# HV_Sense.net
KiCad netlist of a schematic drawn in Altium Designer
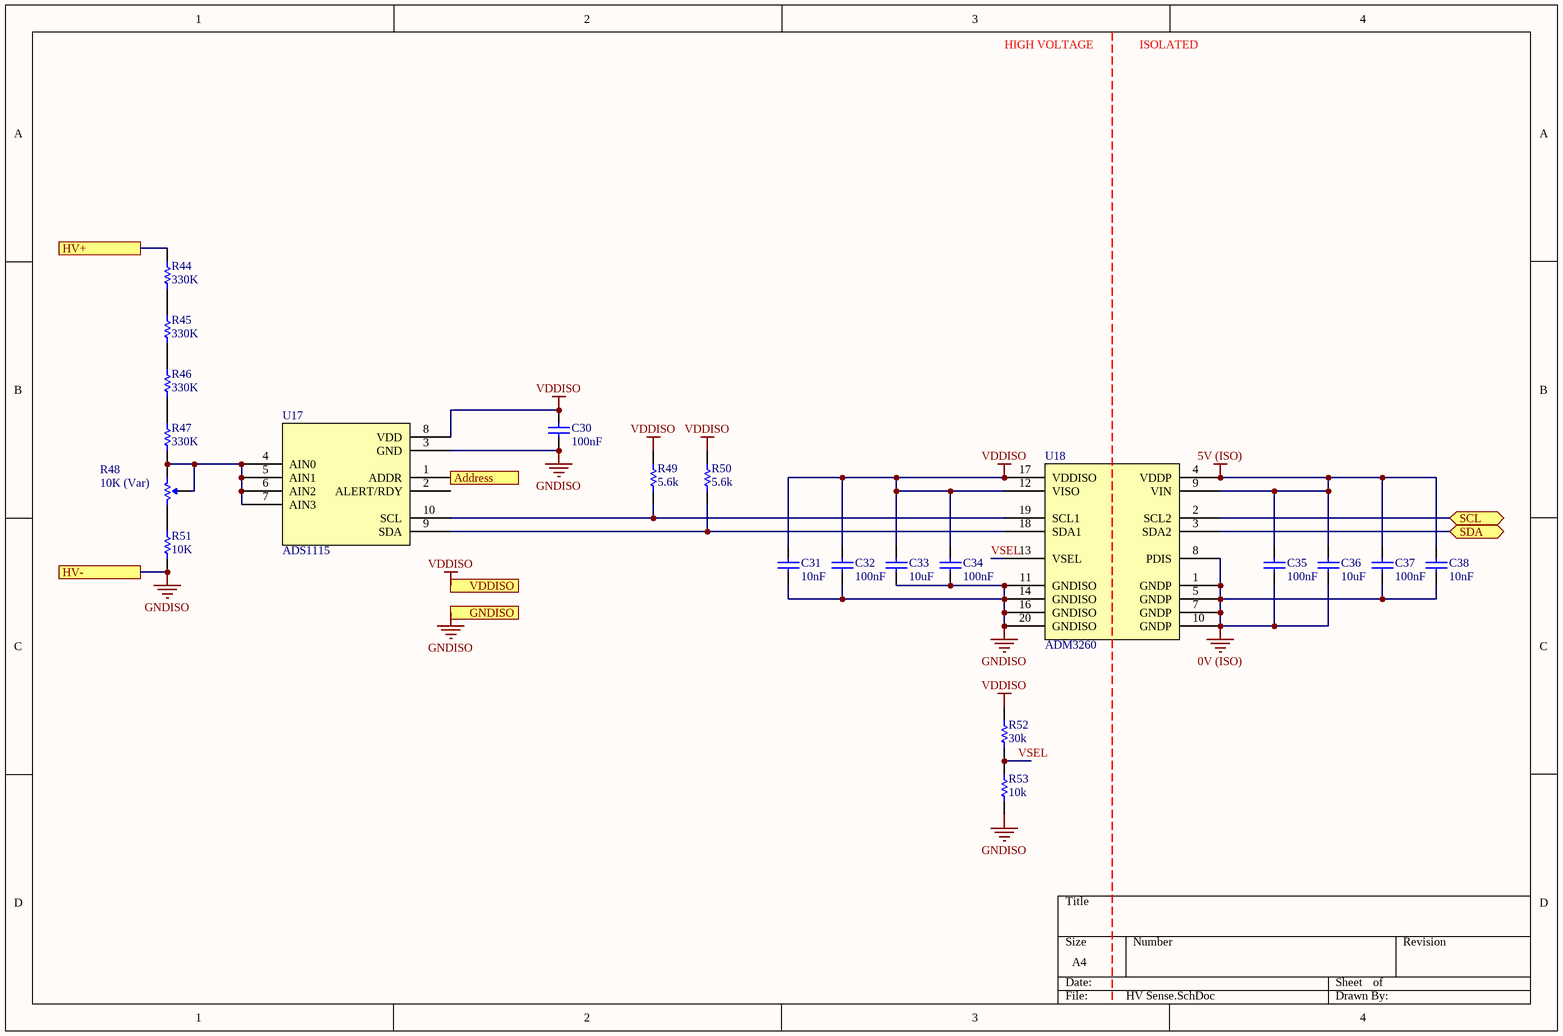
[diagram p0: HV Sense.SchDoc]

(export (version "E")
  (design (tool "Eeschema 10.0.6"))
  (components
    (comp (ref "C30")
      (value "100nF")
      (footprint "0805")
      (fields
        (field (name "PART NUMBER") "GCM21BR71E104KA37L")
        (field (name "TOLERANCE") "10%")
        (field (name "MANUFACTURER") "muRata")
      )
      (libsource (lib "ts_20-standard-library") (part "Capacitor"))
    )
    (comp (ref "C31")
      (value "10nF")
      (footprint "0805")
      (fields
        (field (name "PART NUMBER") "GCM21BR71H103KA37L")
        (field (name "TOLERANCE") "10%")
        (field (name "MANUFACTURER") "muRata")
      )
      (libsource (lib "ts_20-standard-library") (part "Capacitor"))
    )
    (comp (ref "C32")
      (value "100nF")
      (footprint "0805")
      (fields
        (field (name "PART NUMBER") "GCM21BR71E104KA37L")
        (field (name "TOLERANCE") "10%")
        (field (name "MANUFACTURER") "muRata")
      )
      (libsource (lib "ts_20-standard-library") (part "Capacitor"))
    )
    (comp (ref "C33")
      (value "10uF")
      (footprint "0805")
      (fields
        (field (name "PART NUMBER") "GRM21BR6YA106KE43L")
        (field (name "TOLERANCE") "10%")
        (field (name "MANUFACTURER") "muRata")
      )
      (libsource (lib "ts_20-standard-library") (part "Capacitor"))
    )
    (comp (ref "C34")
      (value "100nF")
      (footprint "0805")
      (fields
        (field (name "PART NUMBER") "GCM21BR71E104KA37L")
        (field (name "TOLERANCE") "10%")
        (field (name "MANUFACTURER") "muRata")
      )
      (libsource (lib "ts_20-standard-library") (part "Capacitor"))
    )
    (comp (ref "C35")
      (value "100nF")
      (footprint "0805")
      (fields
        (field (name "PART NUMBER") "GCM21BR71E104KA37L")
        (field (name "TOLERANCE") "10%")
        (field (name "MANUFACTURER") "muRata")
      )
      (libsource (lib "ts_20-standard-library") (part "Capacitor"))
    )
    (comp (ref "C36")
      (value "10uF")
      (footprint "0805")
      (fields
        (field (name "PART NUMBER") "GRM21BR6YA106KE43L")
        (field (name "TOLERANCE") "10%")
        (field (name "MANUFACTURER") "muRata")
      )
      (libsource (lib "ts_20-standard-library") (part "Capacitor"))
    )
    (comp (ref "C37")
      (value "100nF")
      (footprint "0805")
      (fields
        (field (name "PART NUMBER") "GCM21BR71E104KA37L")
        (field (name "TOLERANCE") "10%")
        (field (name "MANUFACTURER") "muRata")
      )
      (libsource (lib "ts_20-standard-library") (part "Capacitor"))
    )
    (comp (ref "C38")
      (value "10nF")
      (footprint "0805")
      (fields
        (field (name "PART NUMBER") "GCM21BR71H103KA37L")
        (field (name "TOLERANCE") "10%")
        (field (name "MANUFACTURER") "muRata")
      )
      (libsource (lib "ts_20-standard-library") (part "Capacitor"))
    )
    (comp (ref "R44")
      (value "330K")
      (footprint "VB 0204")
      (fields
        (field (name "PART NUMBER") "MMA02040C3303FB300")
        (field (name "MANUFACTURER") "Vishay Beyschlag")
        (field (name "TOLERANCE") "0.01")
      )
      (libsource (lib "ts_20-standard-library") (part "Resistor"))
    )
    (comp (ref "R45")
      (value "330K")
      (footprint "VB 0204")
      (fields
        (field (name "PART NUMBER") "MMA02040C3303FB300")
        (field (name "MANUFACTURER") "Vishay Beyschlag")
        (field (name "TOLERANCE") "0.01")
      )
      (libsource (lib "ts_20-standard-library") (part "Resistor"))
    )
    (comp (ref "R46")
      (value "330K")
      (footprint "VB 0204")
      (fields
        (field (name "PART NUMBER") "MMA02040C3303FB300")
        (field (name "MANUFACTURER") "Vishay Beyschlag")
        (field (name "TOLERANCE") "0.01")
      )
      (libsource (lib "ts_20-standard-library") (part "Resistor"))
    )
    (comp (ref "R47")
      (value "330K")
      (footprint "VB 0204")
      (fields
        (field (name "PART NUMBER") "MMA02040C3303FB300")
        (field (name "MANUFACTURER") "Vishay Beyschlag")
        (field (name "TOLERANCE") "0.01")
      )
      (libsource (lib "ts_20-standard-library") (part "Resistor"))
    )
    (comp (ref "R48")
      (value "10K (Var)")
      (footprint "B 3296")
      (fields
        (field (name "PART NUMBER") "3296W-1-103LF")
        (field (name "MANUFACTURER") "Bournes Inc")
        (field (name "TOLERANCE") "0.1")
      )
      (libsource (lib "ts_20-standard-library") (part "Resistor (Potentiometer)"))
    )
    (comp (ref "R49")
      (value "5.6k")
      (footprint "0805")
      (fields
        (field (name "PART NUMBER") "RC0805FR075K6L")
        (field (name "MANUFACTURER") "YAGEO")
        (field (name "TOLERANCE") "0.01")
      )
      (libsource (lib "ts_20-standard-library") (part "Resistor"))
    )
    (comp (ref "R50")
      (value "5.6k")
      (footprint "0805")
      (fields
        (field (name "PART NUMBER") "RC0805FR075K6L")
        (field (name "MANUFACTURER") "YAGEO")
        (field (name "TOLERANCE") "0.01")
      )
      (libsource (lib "ts_20-standard-library") (part "Resistor"))
    )
    (comp (ref "R51")
      (value "10K")
      (footprint "VB 0204")
      (fields
        (field (name "PART NUMBER") "MMA02040C1002FB300")
        (field (name "MANUFACTURER") "Vishay Beyschlag")
        (field (name "TOLERANCE") "0.01")
      )
      (libsource (lib "ts_20-standard-library") (part "Resistor"))
    )
    (comp (ref "R52")
      (value "30k")
      (footprint "0805")
      (fields
        (field (name "PART NUMBER") "RC0805FR0730KL")
        (field (name "MANUFACTURER") "YAGEO")
        (field (name "TOLERANCE") "0.01")
      )
      (libsource (lib "ts_20-standard-library") (part "Resistor"))
    )
    (comp (ref "R53")
      (value "10k")
      (footprint "0805")
      (fields
        (field (name "PART NUMBER") "RC0805FR0710KL")
        (field (name "MANUFACTURER") "YAGEO")
        (field (name "TOLERANCE") "0.01")
      )
      (libsource (lib "ts_20-standard-library") (part "Resistor"))
    )
    (comp (ref "U17")
      (value "ADS1115")
      (footprint "TI 10-VSSOP")
      (description "16 Bit Analog to Digital Converter 2, 4 Input 1 Sigma-Delta 10-VSSOP")
      (fields
        (field (name "MANUFACTURER") "Texas Instruments")
        (field (name "DIGIKEY PART NUMBER") "296-38849-1-ND")
      )
      (libsource (lib "ts_20-standard-library") (part "ADS1115"))
    )
    (comp (ref "U18")
      (value "ADM3260")
      (footprint "AD 20-SSOP")
      (description "I²C Digital Isolator 2500Vrms 2 Channel 25kV/µs CMTI 20-SSOP (0.209\", 5.30mm Width)")
      (fields
        (field (name "MANUFACTURER") "Analog Devices")
        (field (name "DIGIKEY PART NUMBER") "ADM3260ARSZ-RL7CT-ND")
      )
      (libsource (lib "ts_20-standard-library") (part "ADM3260"))
    )
  )
  (nets
    (net (code "1") (name "/Address") (class "Default")
      (node (ref "U17") (pin "1") (pinfunction "ADDR_1") (pintype "passive"))
    )
    (net (code "2") (name "/HV+") (class "Default")
      (node (ref "R44") (pin "2") (pinfunction "2_2") (pintype "passive"))
    )
    (net (code "3") (name "/SCL") (class "Default")
      (node (ref "U18") (pin "2") (pinfunction "SCL2_2") (pintype "passive"))
    )
    (net (code "4") (name "/SDA") (class "Default")
      (node (ref "U18") (pin "3") (pinfunction "SDA2_3") (pintype "passive"))
    )
    (net (code "5") (name "/VSEL") (class "Default")
      (node (ref "R52") (pin "1") (pinfunction "1_1") (pintype "passive"))
      (node (ref "R53") (pin "2") (pinfunction "2_2") (pintype "passive"))
      (node (ref "U18") (pin "13") (pinfunction "VSEL_13") (pintype "passive"))
    )
    (net (code "6") (name "0V (ISO)") (class "Default")
      (node (ref "C35") (pin "1") (pinfunction "1_1") (pintype "passive"))
      (node (ref "C36") (pin "1") (pinfunction "1_1") (pintype "passive"))
      (node (ref "C37") (pin "1") (pinfunction "1_1") (pintype "passive"))
      (node (ref "C38") (pin "1") (pinfunction "1_1") (pintype "passive"))
      (node (ref "U18") (pin "1") (pinfunction "GNDP_1") (pintype "passive"))
      (node (ref "U18") (pin "10") (pinfunction "GNDP_10") (pintype "passive"))
      (node (ref "U18") (pin "5") (pinfunction "GNDP_5") (pintype "passive"))
      (node (ref "U18") (pin "7") (pinfunction "GNDP_7") (pintype "passive"))
      (node (ref "U18") (pin "8") (pinfunction "PDIS_8") (pintype "passive"))
    )
    (net (code "7") (name "5V (ISO)") (class "Default")
      (node (ref "C35") (pin "2") (pinfunction "2_2") (pintype "passive"))
      (node (ref "C36") (pin "2") (pinfunction "2_2") (pintype "passive"))
      (node (ref "C37") (pin "2") (pinfunction "2_2") (pintype "passive"))
      (node (ref "C38") (pin "2") (pinfunction "2_2") (pintype "passive"))
      (node (ref "U18") (pin "4") (pinfunction "VDDP_4") (pintype "passive"))
      (node (ref "U18") (pin "9") (pinfunction "VIN_9") (pintype "passive"))
    )
    (net (code "8") (name "GNDISO") (class "Default")
      (node (ref "C30") (pin "2") (pinfunction "2_2") (pintype "passive"))
      (node (ref "C31") (pin "1") (pinfunction "1_1") (pintype "passive"))
      (node (ref "C32") (pin "1") (pinfunction "1_1") (pintype "passive"))
      (node (ref "C33") (pin "1") (pinfunction "1_1") (pintype "passive"))
      (node (ref "C34") (pin "2") (pinfunction "2_2") (pintype "passive"))
      (node (ref "R51") (pin "1") (pinfunction "1_1") (pintype "passive"))
      (node (ref "R53") (pin "1") (pinfunction "1_1") (pintype "passive"))
      (node (ref "U17") (pin "3") (pinfunction "GND_3") (pintype "passive"))
      (node (ref "U18") (pin "11") (pinfunction "GNDISO_11") (pintype "passive"))
      (node (ref "U18") (pin "14") (pinfunction "GNDISO_14") (pintype "passive"))
      (node (ref "U18") (pin "16") (pinfunction "GNDISO_16") (pintype "passive"))
      (node (ref "U18") (pin "20") (pinfunction "GNDISO_20") (pintype "passive"))
    )
    (net (code "9") (name "Net-(R44-Pad1)") (class "Default")
      (node (ref "R44") (pin "1") (pinfunction "1_1") (pintype "passive"))
      (node (ref "R45") (pin "2") (pinfunction "2_2") (pintype "passive"))
    )
    (net (code "10") (name "Net-(R45-Pad1)") (class "Default")
      (node (ref "R45") (pin "1") (pinfunction "1_1") (pintype "passive"))
      (node (ref "R46") (pin "2") (pinfunction "2_2") (pintype "passive"))
    )
    (net (code "11") (name "Net-(R46-Pad1)") (class "Default")
      (node (ref "R46") (pin "1") (pinfunction "1_1") (pintype "passive"))
      (node (ref "R47") (pin "2") (pinfunction "2_2") (pintype "passive"))
    )
    (net (code "12") (name "Net-(R48-CCW)") (class "Default")
      (node (ref "R48") (pin "1") (pinfunction "CCW_1") (pintype "passive"))
      (node (ref "R51") (pin "2") (pinfunction "2_2") (pintype "passive"))
    )
    (net (code "13") (name "Net-(R48-CW)") (class "Default")
      (node (ref "R47") (pin "1") (pinfunction "1_1") (pintype "passive"))
      (node (ref "R48") (pin "2") (pinfunction "Wiper_2") (pintype "passive"))
      (node (ref "R48") (pin "3") (pinfunction "CW_3") (pintype "passive"))
      (node (ref "U17") (pin "4") (pinfunction "AIN0_4") (pintype "passive"))
      (node (ref "U17") (pin "5") (pinfunction "AIN1_5") (pintype "passive"))
      (node (ref "U17") (pin "6") (pinfunction "AIN2_6") (pintype "passive"))
      (node (ref "U17") (pin "7") (pinfunction "AIN3_7") (pintype "passive"))
    )
    (net (code "14") (name "Net-(U17-SCL)") (class "Default")
      (node (ref "R49") (pin "1") (pinfunction "1_1") (pintype "passive"))
      (node (ref "U17") (pin "10") (pinfunction "SCL_10") (pintype "passive"))
      (node (ref "U18") (pin "19") (pinfunction "SCL1_19") (pintype "passive"))
    )
    (net (code "15") (name "Net-(U17-SDA)") (class "Default")
      (node (ref "R50") (pin "1") (pinfunction "1_1") (pintype "passive"))
      (node (ref "U17") (pin "9") (pinfunction "SDA_9") (pintype "passive"))
      (node (ref "U18") (pin "18") (pinfunction "SDA1_18") (pintype "passive"))
    )
    (net (code "16") (name "VDDISO") (class "Default")
      (node (ref "C30") (pin "1") (pinfunction "1_1") (pintype "passive"))
      (node (ref "C31") (pin "2") (pinfunction "2_2") (pintype "passive"))
      (node (ref "C32") (pin "2") (pinfunction "2_2") (pintype "passive"))
      (node (ref "C33") (pin "2") (pinfunction "2_2") (pintype "passive"))
      (node (ref "C34") (pin "1") (pinfunction "1_1") (pintype "passive"))
      (node (ref "R49") (pin "2") (pinfunction "2_2") (pintype "passive"))
      (node (ref "R50") (pin "2") (pinfunction "2_2") (pintype "passive"))
      (node (ref "R52") (pin "2") (pinfunction "2_2") (pintype "passive"))
      (node (ref "U17") (pin "8") (pinfunction "VDD_8") (pintype "passive"))
      (node (ref "U18") (pin "12") (pinfunction "VISO_12") (pintype "passive"))
      (node (ref "U18") (pin "17") (pinfunction "VDDISO_17") (pintype "passive"))
    )
    (net (code "17") (name "unconnected-(U17-ALERT{slash}RDY-Pad2)") (class "Default")
      (node (ref "U17") (pin "2") (pinfunction "ALERT/RDY_2") (pintype "passive"))
    )
  )
)
